# usb_custom.net
KiCad netlist of a schematic drawn in EAGLE
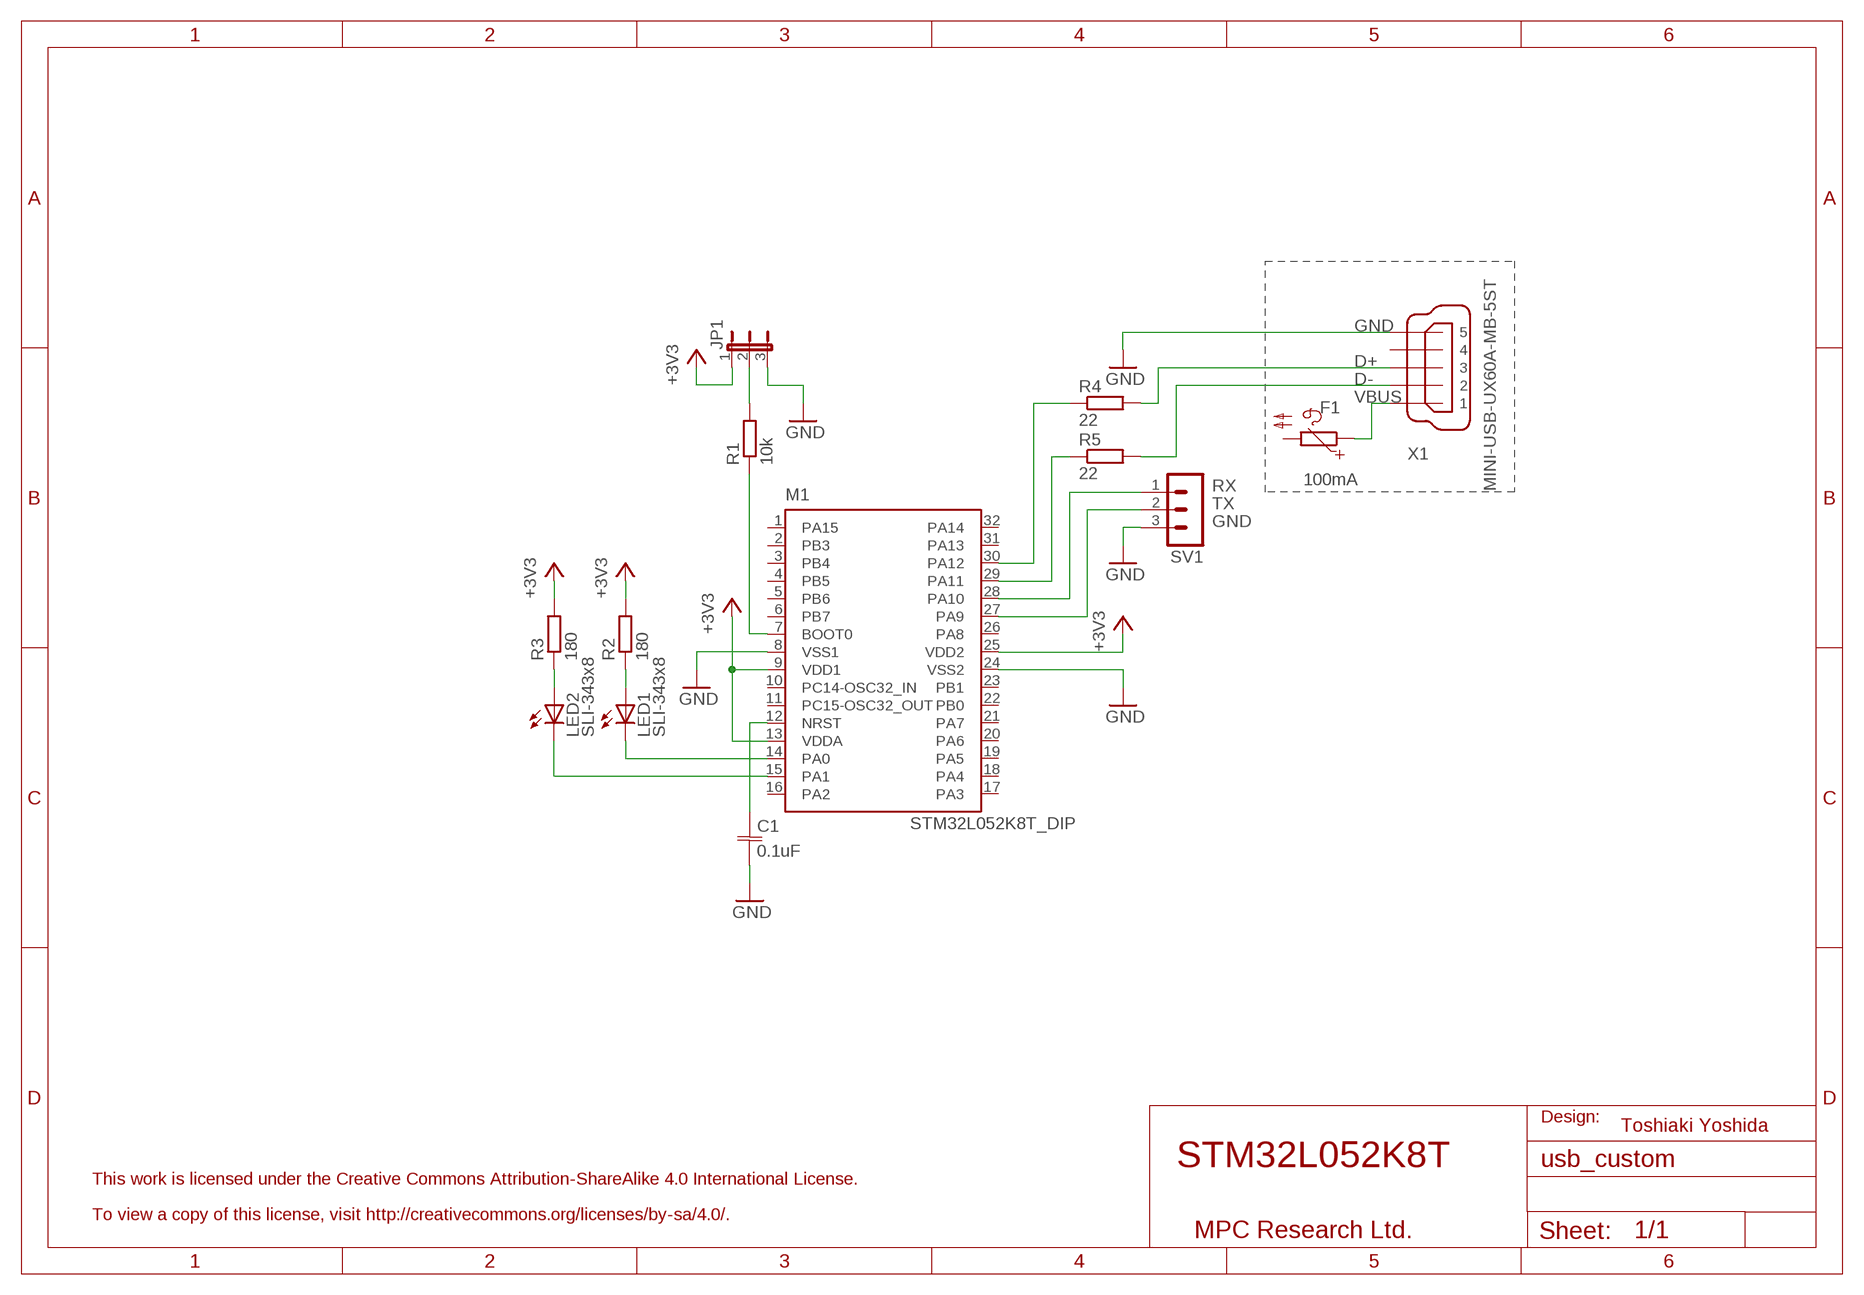
[diagram p0: schematic, sheet 1]

(export (version "E")
  (design (tool "Eeschema 10.0.6"))
  (components
    (comp (ref "C1")
      (value "0.1uF")
      (footprint "eagle-import:C050-024X044")
      (libsource (lib "eagle-import") (part "C-JIS050-024X044"))
    )
    (comp (ref "F1")
      (value "100mA")
      (footprint "eagle-import:1206")
      (libsource (lib "eagle-import") (part "PTC1206"))
    )
    (comp (ref "JP1")
      (value "JP2E")
      (footprint "eagle-import:JP2")
      (libsource (lib "eagle-import") (part "JP2E"))
    )
    (comp (ref "LED1")
      (value "SLI-343x8")
      (footprint "eagle-import:LED3MM")
      (libsource (lib "eagle-import") (part "LED3MM"))
    )
    (comp (ref "LED2")
      (value "SLI-343x8")
      (footprint "eagle-import:LED3MM")
      (libsource (lib "eagle-import") (part "LED3MM"))
    )
    (comp (ref "M1")
      (value "STM32L052K8T_DIP")
      (footprint "eagle-import:DIP32")
      (libsource (lib "eagle-import") (part "STM32L052K8T_DIP"))
    )
    (comp (ref "R1")
      (value "10k")
      (footprint "eagle-import:0207_2V")
      (libsource (lib "eagle-import") (part "R-EU_0207/2V"))
    )
    (comp (ref "R2")
      (value "180")
      (footprint "eagle-import:0207_2V")
      (libsource (lib "eagle-import") (part "R-EU_0207/2V"))
    )
    (comp (ref "R3")
      (value "180")
      (footprint "eagle-import:0207_2V")
      (libsource (lib "eagle-import") (part "R-EU_0207/2V"))
    )
    (comp (ref "R4")
      (value "22")
      (footprint "eagle-import:0207_10")
      (libsource (lib "eagle-import") (part "R-EU_0207/10"))
    )
    (comp (ref "R5")
      (value "22")
      (footprint "eagle-import:0207_10")
      (libsource (lib "eagle-import") (part "R-EU_0207/10"))
    )
    (comp (ref "SV1")
      (value "MA03-1")
      (footprint "eagle-import:MA03-1")
      (libsource (lib "eagle-import") (part "MA03-1"))
    )
    (comp (ref "X1")
      (value "MINI-USB-UX60A-MB-5ST")
      (footprint "eagle-import:UX60A-MB-5ST")
      (libsource (lib "eagle-import") (part "MINI-USB-UX60A-MB-5ST"))
    )
  )
  (nets
    (net (code "1") (name "+3V3") (class "Default")
      (node (ref "JP1") (pin "1") (pinfunction "1_1") (pintype "passive"))
      (node (ref "M1") (pin "13") (pinfunction "VDDA_13") (pintype "power_in"))
      (node (ref "M1") (pin "25") (pinfunction "VDD2_25") (pintype "bidirectional"))
      (node (ref "M1") (pin "9") (pinfunction "VDD1_9") (pintype "power_in"))
      (node (ref "R2") (pin "2") (pinfunction "2_2") (pintype "passive"))
      (node (ref "R3") (pin "2") (pinfunction "2_2") (pintype "passive"))
    )
    (net (code "2") (name "GND") (class "Default")
      (node (ref "C1") (pin "2") (pinfunction "2_2") (pintype "passive"))
      (node (ref "JP1") (pin "3") (pinfunction "3_3") (pintype "passive"))
      (node (ref "M1") (pin "24") (pinfunction "VSS2_24") (pintype "power_in"))
      (node (ref "M1") (pin "8") (pinfunction "VSS1_8") (pintype "power_in"))
      (node (ref "SV1") (pin "3") (pinfunction "3_3") (pintype "passive"))
      (node (ref "X1") (pin "5") (pinfunction "5_5") (pintype "input"))
    )
    (net (code "3") (name "Net-(F1-Pad1)") (class "Default")
      (node (ref "F1") (pin "1") (pinfunction "1_1") (pintype "passive"))
      (node (ref "X1") (pin "1") (pinfunction "1_1") (pintype "input"))
    )
    (net (code "4") (name "Net-(JP1-Pad2)") (class "Default")
      (node (ref "JP1") (pin "2") (pinfunction "2_2") (pintype "passive"))
      (node (ref "R1") (pin "2") (pinfunction "2_2") (pintype "passive"))
    )
    (net (code "5") (name "Net-(LED1-C)") (class "Default")
      (node (ref "LED1") (pin "K") (pinfunction "C_K") (pintype "passive"))
      (node (ref "M1") (pin "14") (pinfunction "PA0_14") (pintype "bidirectional"))
    )
    (net (code "6") (name "Net-(LED1-PadA)") (class "Default")
      (node (ref "LED1") (pin "A") (pinfunction "A_A") (pintype "passive"))
      (node (ref "R2") (pin "1") (pinfunction "1_1") (pintype "passive"))
    )
    (net (code "7") (name "Net-(LED2-C)") (class "Default")
      (node (ref "LED2") (pin "K") (pinfunction "C_K") (pintype "passive"))
      (node (ref "M1") (pin "15") (pinfunction "PA1_15") (pintype "bidirectional"))
    )
    (net (code "8") (name "Net-(LED2-PadA)") (class "Default")
      (node (ref "LED2") (pin "A") (pinfunction "A_A") (pintype "passive"))
      (node (ref "R3") (pin "1") (pinfunction "1_1") (pintype "passive"))
    )
    (net (code "9") (name "Net-(M1-BOOT0)") (class "Default")
      (node (ref "M1") (pin "7") (pinfunction "BOOT0_7") (pintype "bidirectional"))
      (node (ref "R1") (pin "1") (pinfunction "1_1") (pintype "passive"))
    )
    (net (code "10") (name "Net-(M1-NRST)") (class "Default")
      (node (ref "C1") (pin "1") (pinfunction "1_1") (pintype "passive"))
      (node (ref "M1") (pin "12") (pinfunction "NRST_12") (pintype "bidirectional"))
    )
    (net (code "11") (name "Net-(M1-PA9)") (class "Default")
      (node (ref "M1") (pin "27") (pinfunction "PA9_27") (pintype "bidirectional"))
      (node (ref "SV1") (pin "2") (pinfunction "2_2") (pintype "passive"))
    )
    (net (code "12") (name "Net-(M1-PA10)") (class "Default")
      (node (ref "M1") (pin "28") (pinfunction "PA10_28") (pintype "bidirectional"))
      (node (ref "SV1") (pin "1") (pinfunction "1_1") (pintype "passive"))
    )
    (net (code "13") (name "Net-(M1-PA11)") (class "Default")
      (node (ref "M1") (pin "29") (pinfunction "PA11_29") (pintype "bidirectional"))
      (node (ref "R5") (pin "1") (pinfunction "1_1") (pintype "passive"))
    )
    (net (code "14") (name "Net-(M1-PA12)") (class "Default")
      (node (ref "M1") (pin "30") (pinfunction "PA12_30") (pintype "bidirectional"))
      (node (ref "R4") (pin "1") (pinfunction "1_1") (pintype "passive"))
    )
    (net (code "15") (name "Net-(R4-Pad2)") (class "Default")
      (node (ref "R4") (pin "2") (pinfunction "2_2") (pintype "passive"))
      (node (ref "X1") (pin "3") (pinfunction "3_3") (pintype "input"))
    )
    (net (code "16") (name "Net-(R5-Pad2)") (class "Default")
      (node (ref "R5") (pin "2") (pinfunction "2_2") (pintype "passive"))
      (node (ref "X1") (pin "2") (pinfunction "2_2") (pintype "input"))
    )
    (net (code "17") (name "unconnected-(F1-Pad2)") (class "Default")
      (node (ref "F1") (pin "2") (pinfunction "2_2") (pintype "passive"))
    )
    (net (code "18") (name "unconnected-(M1-PA2-Pad16)") (class "Default")
      (node (ref "M1") (pin "16") (pinfunction "PA2_16") (pintype "bidirectional"))
    )
    (net (code "19") (name "unconnected-(M1-PA3-Pad17)") (class "Default")
      (node (ref "M1") (pin "17") (pinfunction "PA3_17") (pintype "bidirectional"))
    )
    (net (code "20") (name "unconnected-(M1-PA4-Pad18)") (class "Default")
      (node (ref "M1") (pin "18") (pinfunction "PA4_18") (pintype "bidirectional"))
    )
    (net (code "21") (name "unconnected-(M1-PA5-Pad19)") (class "Default")
      (node (ref "M1") (pin "19") (pinfunction "PA5_19") (pintype "bidirectional"))
    )
    (net (code "22") (name "unconnected-(M1-PA6-Pad20)") (class "Default")
      (node (ref "M1") (pin "20") (pinfunction "PA6_20") (pintype "bidirectional"))
    )
    (net (code "23") (name "unconnected-(M1-PA7-Pad21)") (class "Default")
      (node (ref "M1") (pin "21") (pinfunction "PA7_21") (pintype "bidirectional"))
    )
    (net (code "24") (name "unconnected-(M1-PA8-Pad26)") (class "Default")
      (node (ref "M1") (pin "26") (pinfunction "PA8_26") (pintype "bidirectional"))
    )
    (net (code "25") (name "unconnected-(M1-PA13-Pad31)") (class "Default")
      (node (ref "M1") (pin "31") (pinfunction "PA13_31") (pintype "bidirectional"))
    )
    (net (code "26") (name "unconnected-(M1-PA14-Pad32)") (class "Default")
      (node (ref "M1") (pin "32") (pinfunction "PA14_32") (pintype "bidirectional"))
    )
    (net (code "27") (name "unconnected-(M1-PA15-Pad1)") (class "Default")
      (node (ref "M1") (pin "1") (pinfunction "PA15_1") (pintype "bidirectional"))
    )
    (net (code "28") (name "unconnected-(M1-PB0-Pad22)") (class "Default")
      (node (ref "M1") (pin "22") (pinfunction "PB0_22") (pintype "bidirectional"))
    )
    (net (code "29") (name "unconnected-(M1-PB1-Pad23)") (class "Default")
      (node (ref "M1") (pin "23") (pinfunction "PB1_23") (pintype "bidirectional"))
    )
    (net (code "30") (name "unconnected-(M1-PB3-Pad2)") (class "Default")
      (node (ref "M1") (pin "2") (pinfunction "PB3_2") (pintype "bidirectional"))
    )
    (net (code "31") (name "unconnected-(M1-PB4-Pad3)") (class "Default")
      (node (ref "M1") (pin "3") (pinfunction "PB4_3") (pintype "bidirectional"))
    )
    (net (code "32") (name "unconnected-(M1-PB5-Pad4)") (class "Default")
      (node (ref "M1") (pin "4") (pinfunction "PB5_4") (pintype "bidirectional"))
    )
    (net (code "33") (name "unconnected-(M1-PB6-Pad5)") (class "Default")
      (node (ref "M1") (pin "5") (pinfunction "PB6_5") (pintype "bidirectional"))
    )
    (net (code "34") (name "unconnected-(M1-PB7-Pad6)") (class "Default")
      (node (ref "M1") (pin "6") (pinfunction "PB7_6") (pintype "bidirectional"))
    )
    (net (code "35") (name "unconnected-(M1-PC14-OSC32_IN-Pad10)") (class "Default")
      (node (ref "M1") (pin "10") (pinfunction "PC14-OSC32_IN_10") (pintype "bidirectional"))
    )
    (net (code "36") (name "unconnected-(M1-PC15-OSC32_OUT-Pad11)") (class "Default")
      (node (ref "M1") (pin "11") (pinfunction "PC15-OSC32_OUT_11") (pintype "bidirectional"))
    )
    (net (code "37") (name "unconnected-(X1-Pad4)") (class "Default")
      (node (ref "X1") (pin "4") (pinfunction "4_4") (pintype "input"))
    )
  )
)
